# motorShield.net
KiCad netlist of a schematic drawn in EAGLE
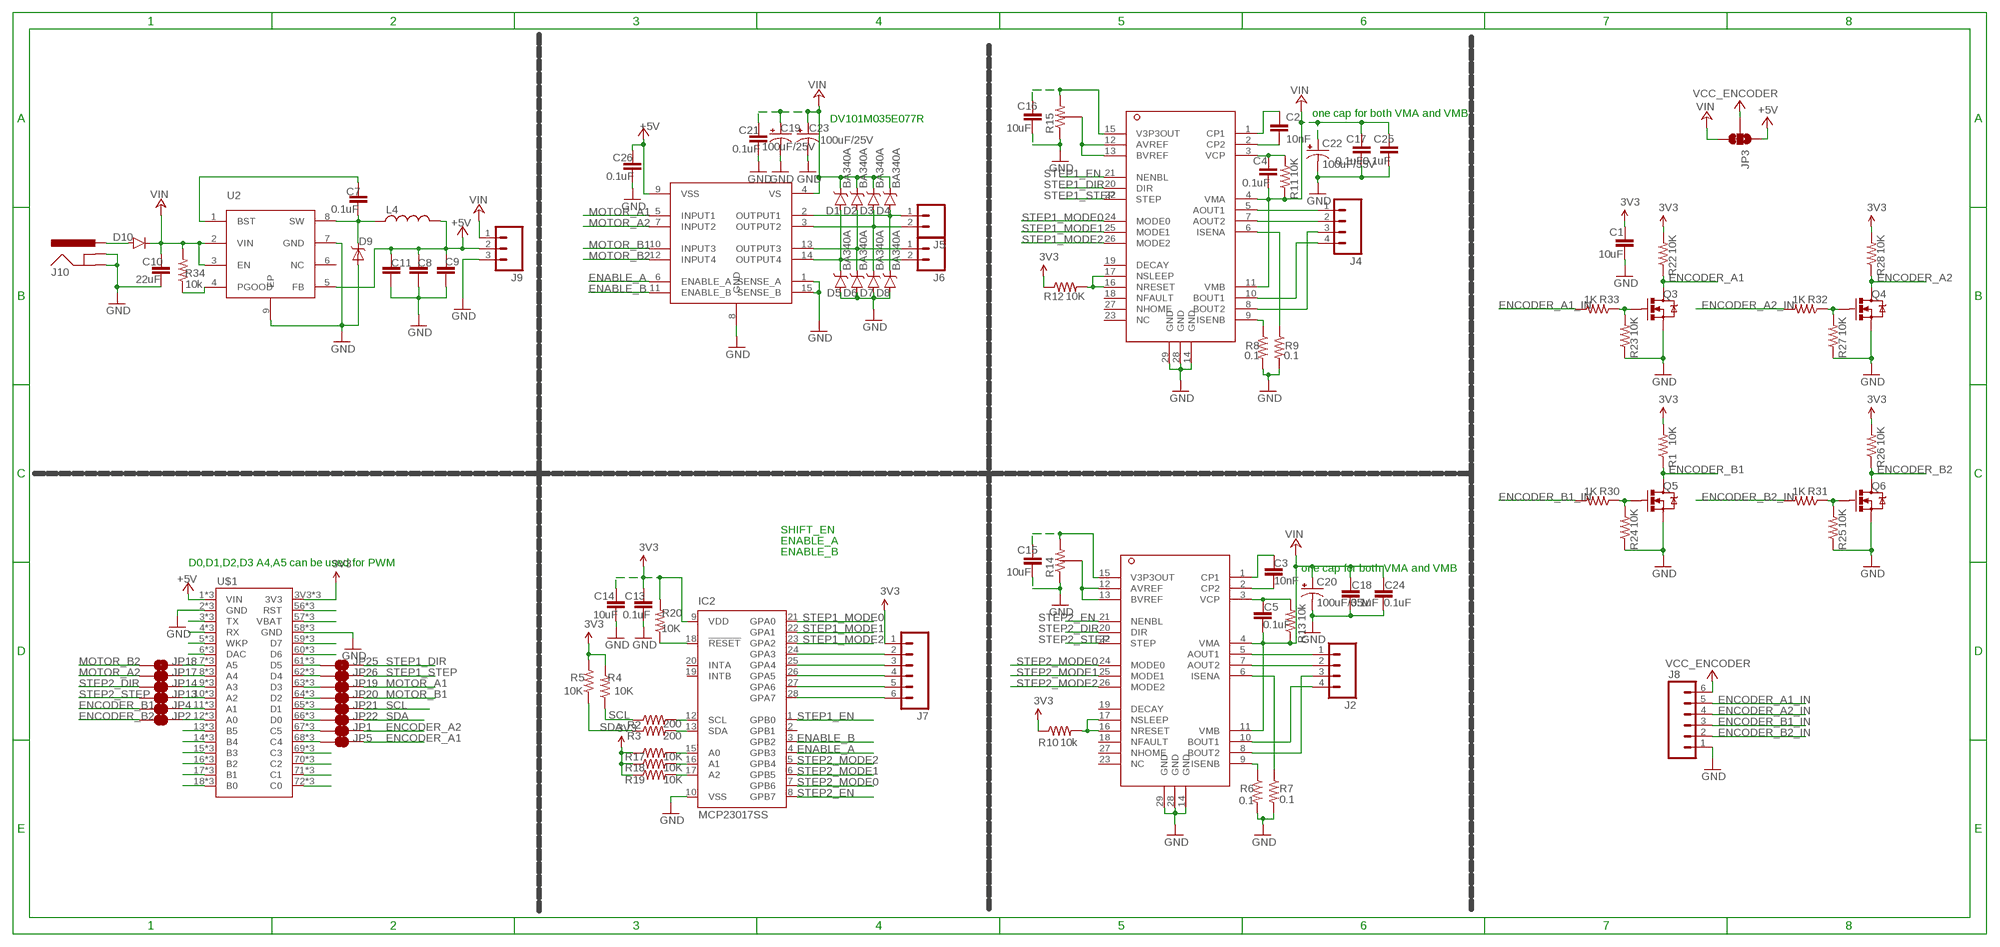
[diagram p0: schematic, sheet 1]

(export (version "E")
  (design (tool "Eeschema 10.0.6"))
  (components
    (comp (ref "C1")
      (value "10uF")
      (footprint "eagle-import:0603")
      (libsource (lib "eagle-import") (part "CAP_NONE_POL"))
    )
    (comp (ref "C2")
      (value "10nF")
      (footprint "eagle-import:0603")
      (libsource (lib "eagle-import") (part "CAP_NONE_POL"))
    )
    (comp (ref "C3")
      (value "10nF")
      (footprint "eagle-import:0603")
      (libsource (lib "eagle-import") (part "CAP_NONE_POL"))
    )
    (comp (ref "C4")
      (value "0.1uF")
      (footprint "eagle-import:0603")
      (libsource (lib "eagle-import") (part "CAP_NONE_POL"))
    )
    (comp (ref "C5")
      (value "0.1uF")
      (footprint "eagle-import:0603")
      (libsource (lib "eagle-import") (part "CAP_NONE_POL"))
    )
    (comp (ref "C7")
      (value "0.1uF")
      (footprint "eagle-import:0603-CAP")
      (libsource (lib "eagle-import") (part "0.1UF-100V-10%(0603)"))
    )
    (comp (ref "C8")
      (value "10UF10V10%(0805)")
      (footprint "eagle-import:0805-CAP")
      (libsource (lib "eagle-import") (part "10UF10V10%(0805)"))
    )
    (comp (ref "C9")
      (value "10UF10V10%(0805)")
      (footprint "eagle-import:0805-CAP")
      (libsource (lib "eagle-import") (part "10UF10V10%(0805)"))
    )
    (comp (ref "C10")
      (value "22uF")
      (footprint "eagle-import:1210")
      (libsource (lib "eagle-import") (part "22UF-16V-20%-(1210)"))
    )
    (comp (ref "C11")
      (value "10UF10V10%(0805)")
      (footprint "eagle-import:0805-CAP")
      (libsource (lib "eagle-import") (part "10UF10V10%(0805)"))
    )
    (comp (ref "C13")
      (value "0.1uF")
      (footprint "eagle-import:0603")
      (libsource (lib "eagle-import") (part "CAP_NONE_POL"))
    )
    (comp (ref "C14")
      (value "10uF")
      (footprint "eagle-import:0603")
      (libsource (lib "eagle-import") (part "CAP_NONE_POL"))
    )
    (comp (ref "C15")
      (value "10uF")
      (footprint "eagle-import:0603")
      (libsource (lib "eagle-import") (part "CAP_NONE_POL"))
    )
    (comp (ref "C16")
      (value "10uF")
      (footprint "eagle-import:0603")
      (libsource (lib "eagle-import") (part "CAP_NONE_POL"))
    )
    (comp (ref "C17")
      (value "0.1uF")
      (footprint "eagle-import:0603")
      (libsource (lib "eagle-import") (part "CAP_NONE_POL"))
    )
    (comp (ref "C18")
      (value "0.1uF")
      (footprint "eagle-import:0603")
      (libsource (lib "eagle-import") (part "CAP_NONE_POL"))
    )
    (comp (ref "C19")
      (value "100uF/25V")
      (footprint "eagle-import:PANASONIC_D")
      (libsource (lib "eagle-import") (part "CAP_POLD"))
    )
    (comp (ref "C20")
      (value "100uF/35V")
      (footprint "eagle-import:PANASONIC_D")
      (libsource (lib "eagle-import") (part "CAP_POLD"))
    )
    (comp (ref "C21")
      (value "0.1uF")
      (footprint "eagle-import:0603")
      (libsource (lib "eagle-import") (part "CAP_NONE_POL"))
    )
    (comp (ref "C22")
      (value "100uF/35V")
      (footprint "eagle-import:PANASONIC_D")
      (libsource (lib "eagle-import") (part "CAP_POLD"))
    )
    (comp (ref "C23")
      (value "100uF/25V")
      (footprint "eagle-import:PANASONIC_D")
      (libsource (lib "eagle-import") (part "CAP_POLD"))
    )
    (comp (ref "C24")
      (value "0.1uF")
      (footprint "eagle-import:0603")
      (libsource (lib "eagle-import") (part "CAP_NONE_POL"))
    )
    (comp (ref "C25")
      (value "0.1uF")
      (footprint "eagle-import:0603")
      (libsource (lib "eagle-import") (part "CAP_NONE_POL"))
    )
    (comp (ref "C26")
      (value "0.1uF")
      (footprint "eagle-import:0603")
      (libsource (lib "eagle-import") (part "CAP_NONE_POL"))
    )
    (comp (ref "D1")
      (value "BA340A")
      (footprint "eagle-import:SMA-DIODE")
      (libsource (lib "eagle-import") (part "B340A"))
    )
    (comp (ref "D2")
      (value "BA340A")
      (footprint "eagle-import:SMA-DIODE")
      (libsource (lib "eagle-import") (part "B340A"))
    )
    (comp (ref "D3")
      (value "BA340A")
      (footprint "eagle-import:SMA-DIODE")
      (libsource (lib "eagle-import") (part "B340A"))
    )
    (comp (ref "D4")
      (value "BA340A")
      (footprint "eagle-import:SMA-DIODE")
      (libsource (lib "eagle-import") (part "B340A"))
    )
    (comp (ref "D5")
      (value "BA340A")
      (footprint "eagle-import:SMA-DIODE")
      (libsource (lib "eagle-import") (part "B340A"))
    )
    (comp (ref "D6")
      (value "BA340A")
      (footprint "eagle-import:SMA-DIODE")
      (libsource (lib "eagle-import") (part "B340A"))
    )
    (comp (ref "D7")
      (value "BA340A")
      (footprint "eagle-import:SMA-DIODE")
      (libsource (lib "eagle-import") (part "B340A"))
    )
    (comp (ref "D8")
      (value "BA340A")
      (footprint "eagle-import:SMA-DIODE")
      (libsource (lib "eagle-import") (part "B340A"))
    )
    (comp (ref "D9")
      (value "DIODE_SCHOTTKYA")
      (footprint "eagle-import:DIODE_SMA")
      (libsource (lib "eagle-import") (part "DIODE_SCHOTTKYA"))
    )
    (comp (ref "D10")
      (value "DIODEB")
      (footprint "eagle-import:DIODE-DO-220AA_NT(SMP)")
      (libsource (lib "eagle-import") (part "DIODEB"))
    )
    (comp (ref "IC2")
      (value "MCP23017SS")
      (footprint "eagle-import:SSOP28")
      (libsource (lib "eagle-import") (part "MCP23017SS"))
    )
    (comp (ref "J2")
      (value "M04SCREW")
      (footprint "eagle-import:SCREWTERMINAL-3.5MM-4")
      (libsource (lib "eagle-import") (part "M04SCREW"))
    )
    (comp (ref "J4")
      (value "M04SCREW")
      (footprint "eagle-import:SCREWTERMINAL-3.5MM-4")
      (libsource (lib "eagle-import") (part "M04SCREW"))
    )
    (comp (ref "J5")
      (value "M023.5MM_LOCK")
      (footprint "eagle-import:SCREWTERMINAL-3.5MM-2_LOCK")
      (libsource (lib "eagle-import") (part "M023.5MM_LOCK"))
    )
    (comp (ref "J6")
      (value "M023.5MM_LOCK")
      (footprint "eagle-import:SCREWTERMINAL-3.5MM-2_LOCK")
      (libsource (lib "eagle-import") (part "M023.5MM_LOCK"))
    )
    (comp (ref "J7")
      (value "M06POLAR")
      (footprint "eagle-import:MOLEX-1X6")
      (libsource (lib "eagle-import") (part "M06POLAR"))
    )
    (comp (ref "J8")
      (value "M06POLAR")
      (footprint "eagle-import:MOLEX-1X6")
      (libsource (lib "eagle-import") (part "M06POLAR"))
    )
    (comp (ref "J9")
      (value "M03SCREW")
      (footprint "eagle-import:SCREWTERMINAL-3.5MM-3")
      (libsource (lib "eagle-import") (part "M03SCREW"))
    )
    (comp (ref "J10")
      (value "POWER_JACKPTH")
      (footprint "eagle-import:POWER_JACK_PTH")
      (libsource (lib "eagle-import") (part "POWER_JACKPTH"))
    )
    (comp (ref "JP1")
      (value "JUMPER-PAD-2-NC_BY_TRACENO_SILK")
      (footprint "eagle-import:PAD-JUMPER-2-NC_BY_TRACE_NO_SILK")
      (libsource (lib "eagle-import") (part "JUMPER-PAD-2-NC_BY_TRACENO_SILK"))
    )
    (comp (ref "JP2")
      (value "JUMPER-PAD-2-NC_BY_TRACENO_SILK")
      (footprint "eagle-import:PAD-JUMPER-2-NC_BY_TRACE_NO_SILK")
      (libsource (lib "eagle-import") (part "JUMPER-PAD-2-NC_BY_TRACENO_SILK"))
    )
    (comp (ref "JP3")
      (value "JUMPER-PAD-3-2OF3_NC_BY_TRACE_LARGE")
      (footprint "eagle-import:PAD-JUMPER-3-2OF3_NC_BY_TRACE_YES_SILK_LARGE")
      (libsource (lib "eagle-import") (part "JUMPER-PAD-3-2OF3_NC_BY_TRACE_LARGE"))
    )
    (comp (ref "JP4")
      (value "JUMPER-PAD-2-NC_BY_TRACENO_SILK")
      (footprint "eagle-import:PAD-JUMPER-2-NC_BY_TRACE_NO_SILK")
      (libsource (lib "eagle-import") (part "JUMPER-PAD-2-NC_BY_TRACENO_SILK"))
    )
    (comp (ref "JP5")
      (value "JUMPER-PAD-2-NC_BY_TRACENO_SILK")
      (footprint "eagle-import:PAD-JUMPER-2-NC_BY_TRACE_NO_SILK")
      (libsource (lib "eagle-import") (part "JUMPER-PAD-2-NC_BY_TRACENO_SILK"))
    )
    (comp (ref "JP13")
      (value "JUMPER-PAD-2-NC_BY_TRACENO_SILK")
      (footprint "eagle-import:PAD-JUMPER-2-NC_BY_TRACE_NO_SILK")
      (libsource (lib "eagle-import") (part "JUMPER-PAD-2-NC_BY_TRACENO_SILK"))
    )
    (comp (ref "JP14")
      (value "JUMPER-PAD-2-NC_BY_TRACENO_SILK")
      (footprint "eagle-import:PAD-JUMPER-2-NC_BY_TRACE_NO_SILK")
      (libsource (lib "eagle-import") (part "JUMPER-PAD-2-NC_BY_TRACENO_SILK"))
    )
    (comp (ref "JP17")
      (value "JUMPER-PAD-2-NC_BY_TRACENO_SILK")
      (footprint "eagle-import:PAD-JUMPER-2-NC_BY_TRACE_NO_SILK")
      (libsource (lib "eagle-import") (part "JUMPER-PAD-2-NC_BY_TRACENO_SILK"))
    )
    (comp (ref "JP18")
      (value "JUMPER-PAD-2-NC_BY_TRACENO_SILK")
      (footprint "eagle-import:PAD-JUMPER-2-NC_BY_TRACE_NO_SILK")
      (libsource (lib "eagle-import") (part "JUMPER-PAD-2-NC_BY_TRACENO_SILK"))
    )
    (comp (ref "JP19")
      (value "JUMPER-PAD-2-NC_BY_TRACENO_SILK")
      (footprint "eagle-import:PAD-JUMPER-2-NC_BY_TRACE_NO_SILK")
      (libsource (lib "eagle-import") (part "JUMPER-PAD-2-NC_BY_TRACENO_SILK"))
    )
    (comp (ref "JP20")
      (value "JUMPER-PAD-2-NC_BY_TRACENO_SILK")
      (footprint "eagle-import:PAD-JUMPER-2-NC_BY_TRACE_NO_SILK")
      (libsource (lib "eagle-import") (part "JUMPER-PAD-2-NC_BY_TRACENO_SILK"))
    )
    (comp (ref "JP21")
      (value "JUMPER-PAD-2-NC_BY_TRACENO_SILK")
      (footprint "eagle-import:PAD-JUMPER-2-NC_BY_TRACE_NO_SILK")
      (libsource (lib "eagle-import") (part "JUMPER-PAD-2-NC_BY_TRACENO_SILK"))
    )
    (comp (ref "JP22")
      (value "JUMPER-PAD-2-NC_BY_TRACENO_SILK")
      (footprint "eagle-import:PAD-JUMPER-2-NC_BY_TRACE_NO_SILK")
      (libsource (lib "eagle-import") (part "JUMPER-PAD-2-NC_BY_TRACENO_SILK"))
    )
    (comp (ref "JP25")
      (value "JUMPER-PAD-2-NC_BY_TRACENO_SILK")
      (footprint "eagle-import:PAD-JUMPER-2-NC_BY_TRACE_NO_SILK")
      (libsource (lib "eagle-import") (part "JUMPER-PAD-2-NC_BY_TRACENO_SILK"))
    )
    (comp (ref "JP26")
      (value "JUMPER-PAD-2-NC_BY_TRACENO_SILK")
      (footprint "eagle-import:PAD-JUMPER-2-NC_BY_TRACE_NO_SILK")
      (libsource (lib "eagle-import") (part "JUMPER-PAD-2-NC_BY_TRACENO_SILK"))
    )
    (comp (ref "L4")
      (value "INDUCTOR4818")
      (footprint "eagle-import:I4818")
      (libsource (lib "eagle-import") (part "INDUCTOR4818"))
    )
    (comp (ref "Q3")
      (value "MOSFET-NCHANNELBSS138")
      (footprint "eagle-import:SOT23")
      (libsource (lib "eagle-import") (part "MOSFET-NCHANNELBSS138"))
    )
    (comp (ref "Q4")
      (value "MOSFET-NCHANNELBSS138")
      (footprint "eagle-import:SOT23")
      (libsource (lib "eagle-import") (part "MOSFET-NCHANNELBSS138"))
    )
    (comp (ref "Q5")
      (value "MOSFET-NCHANNELBSS138")
      (footprint "eagle-import:SOT23")
      (libsource (lib "eagle-import") (part "MOSFET-NCHANNELBSS138"))
    )
    (comp (ref "Q6")
      (value "MOSFET-NCHANNELBSS138")
      (footprint "eagle-import:SOT23")
      (libsource (lib "eagle-import") (part "MOSFET-NCHANNELBSS138"))
    )
    (comp (ref "R1")
      (value "10K")
      (footprint "eagle-import:R0603")
      (libsource (lib "eagle-import") (part "R-US_A"))
    )
    (comp (ref "R2")
      (value "200")
      (footprint "eagle-import:R0603")
      (libsource (lib "eagle-import") (part "R-US_A"))
    )
    (comp (ref "R3")
      (value "200")
      (footprint "eagle-import:R0603")
      (libsource (lib "eagle-import") (part "R-US_A"))
    )
    (comp (ref "R4")
      (value "10K")
      (footprint "eagle-import:R0603")
      (libsource (lib "eagle-import") (part "R-US_A"))
    )
    (comp (ref "R5")
      (value "10K")
      (footprint "eagle-import:R0603")
      (libsource (lib "eagle-import") (part "R-US_A"))
    )
    (comp (ref "R6")
      (value "0.1")
      (footprint "eagle-import:M1206")
      (libsource (lib "eagle-import") (part "R-US_M1206"))
    )
    (comp (ref "R7")
      (value "0.1")
      (footprint "eagle-import:M1206")
      (libsource (lib "eagle-import") (part "R-US_M1206"))
    )
    (comp (ref "R8")
      (value "0.1")
      (footprint "eagle-import:M1206")
      (libsource (lib "eagle-import") (part "R-US_M1206"))
    )
    (comp (ref "R9")
      (value "0.1")
      (footprint "eagle-import:M1206")
      (libsource (lib "eagle-import") (part "R-US_M1206"))
    )
    (comp (ref "R10")
      (value "10k")
      (footprint "eagle-import:R0603")
      (libsource (lib "eagle-import") (part "R-US_A"))
    )
    (comp (ref "R11")
      (value "10K")
      (footprint "eagle-import:R0603")
      (libsource (lib "eagle-import") (part "R-US_A"))
    )
    (comp (ref "R12")
      (value "10K")
      (footprint "eagle-import:R0603")
      (libsource (lib "eagle-import") (part "R-US_A"))
    )
    (comp (ref "R13")
      (value "10k")
      (footprint "eagle-import:R0603")
      (libsource (lib "eagle-import") (part "R-US_A"))
    )
    (comp (ref "R14")
      (value "POTENTIAL_RESISTOR")
      (footprint "eagle-import:POTENTIAL_RESISTOR_2")
      (libsource (lib "eagle-import") (part "POTENTIAL_RESISTOR"))
    )
    (comp (ref "R15")
      (value "POTENTIAL_RESISTOR")
      (footprint "eagle-import:POTENTIAL_RESISTOR_2")
      (libsource (lib "eagle-import") (part "POTENTIAL_RESISTOR"))
    )
    (comp (ref "R17")
      (value "10K")
      (footprint "eagle-import:R0603")
      (libsource (lib "eagle-import") (part "R-US_A"))
    )
    (comp (ref "R18")
      (value "10K")
      (footprint "eagle-import:R0603")
      (libsource (lib "eagle-import") (part "R-US_A"))
    )
    (comp (ref "R19")
      (value "10K")
      (footprint "eagle-import:R0603")
      (libsource (lib "eagle-import") (part "R-US_A"))
    )
    (comp (ref "R20")
      (value "10K")
      (footprint "eagle-import:R0603")
      (libsource (lib "eagle-import") (part "R-US_A"))
    )
    (comp (ref "R22")
      (value "10K")
      (footprint "eagle-import:R0603")
      (libsource (lib "eagle-import") (part "R-US_A"))
    )
    (comp (ref "R23")
      (value "10K")
      (footprint "eagle-import:R0603")
      (libsource (lib "eagle-import") (part "R-US_A"))
    )
    (comp (ref "R24")
      (value "10K")
      (footprint "eagle-import:R0603")
      (libsource (lib "eagle-import") (part "R-US_A"))
    )
    (comp (ref "R25")
      (value "10K")
      (footprint "eagle-import:R0603")
      (libsource (lib "eagle-import") (part "R-US_A"))
    )
    (comp (ref "R26")
      (value "10K")
      (footprint "eagle-import:R0603")
      (libsource (lib "eagle-import") (part "R-US_A"))
    )
    (comp (ref "R27")
      (value "10K")
      (footprint "eagle-import:R0603")
      (libsource (lib "eagle-import") (part "R-US_A"))
    )
    (comp (ref "R28")
      (value "10K")
      (footprint "eagle-import:R0603")
      (libsource (lib "eagle-import") (part "R-US_A"))
    )
    (comp (ref "R30")
      (value "1K")
      (footprint "eagle-import:R0603")
      (libsource (lib "eagle-import") (part "R-US_A"))
    )
    (comp (ref "R31")
      (value "1K")
      (footprint "eagle-import:R0603")
      (libsource (lib "eagle-import") (part "R-US_A"))
    )
    (comp (ref "R32")
      (value "1K")
      (footprint "eagle-import:R0603")
      (libsource (lib "eagle-import") (part "R-US_A"))
    )
    (comp (ref "R33")
      (value "1K")
      (footprint "eagle-import:R0603")
      (libsource (lib "eagle-import") (part "R-US_A"))
    )
    (comp (ref "R34")
      (value "10k")
      (footprint "eagle-import:0603-RES")
      (libsource (lib "eagle-import") (part "20OHM1/10W1%(0603)SMD"))
    )
    (comp (ref "U$1")
      (value "ELECTRONDUALROW")
      (footprint "eagle-import:ELECTRON_DUAL-ROW")
      (libsource (lib "eagle-import") (part "ELECTRONDUALROW"))
    )
    (comp (ref "U2")
      (value "ADP2303")
      (footprint "eagle-import:ADP2302")
      (libsource (lib "eagle-import") (part "ADP2303"))
    )
    (comp (ref "U?1")
      (value "DRV8825")
      (footprint "eagle-import:DRV8825")
      (libsource (lib "eagle-import") (part "DRV8825"))
    )
    (comp (ref "U?2")
      (value "L298")
      (footprint "eagle-import:L298")
      (libsource (lib "eagle-import") (part "L298"))
    )
    (comp (ref "U?3")
      (value "DRV8825")
      (footprint "eagle-import:DRV8825")
      (libsource (lib "eagle-import") (part "DRV8825"))
    )
  )
  (nets
    (net (code "1") (name "+5V") (class "Default")
      (node (ref "C11") (pin "1") (pinfunction "1_1") (pintype "passive"))
      (node (ref "C26") (pin "1") (pinfunction "ANODE_1") (pintype "passive"))
      (node (ref "C8") (pin "2") (pinfunction "2_2") (pintype "passive"))
      (node (ref "C9") (pin "2") (pinfunction "2_2") (pintype "passive"))
      (node (ref "J8") (pin "6") (pinfunction "6_6") (pintype "passive"))
      (node (ref "J9") (pin "2") (pinfunction "2_2") (pintype "passive"))
      (node (ref "JP3") (pin "1") (pinfunction "1_1") (pintype "passive"))
      (node (ref "JP3") (pin "2") (pinfunction "2_2") (pintype "passive"))
      (node (ref "L4") (pin "2") (pinfunction "2_2") (pintype "passive"))
      (node (ref "U$1") (pin "1") (pinfunction "VIN_1") (pintype "power_in"))
      (node (ref "U$1") (pin "37") (pinfunction "VIN_37") (pintype "power_in"))
      (node (ref "U$1") (pin "VIN") (pinfunction "VIN_VIN") (pintype "power_in"))
      (node (ref "U2") (pin "5") (pinfunction "FB_5") (pintype "bidirectional"))
      (node (ref "U?2") (pin "9") (pinfunction "VSS_9") (pintype "bidirectional"))
    )
    (net (code "2") (name "/ENABLE_A") (class "Default")
      (node (ref "IC2") (pin "4") (pinfunction "GPB3_4") (pintype "bidirectional"))
      (node (ref "U?2") (pin "6") (pinfunction "ENABLE_A_6") (pintype "bidirectional"))
    )
    (net (code "3") (name "/ENABLE_B") (class "Default")
      (node (ref "IC2") (pin "3") (pinfunction "GPB2_3") (pintype "bidirectional"))
      (node (ref "U?2") (pin "11") (pinfunction "ENABLE_B_11") (pintype "bidirectional"))
    )
    (net (code "4") (name "/ENCODER_A1") (class "Default")
      (node (ref "JP5") (pin "2") (pinfunction "2_2") (pintype "passive"))
      (node (ref "Q3") (pin "3") (pinfunction "D_3") (pintype "passive"))
      (node (ref "R22") (pin "1") (pinfunction "1_1") (pintype "passive"))
    )
    (net (code "5") (name "/ENCODER_A1_IN") (class "Default")
      (node (ref "J8") (pin "5") (pinfunction "5_5") (pintype "passive"))
      (node (ref "R33") (pin "2") (pinfunction "2_2") (pintype "passive"))
    )
    (net (code "6") (name "/ENCODER_A2") (class "Default")
      (node (ref "JP1") (pin "2") (pinfunction "2_2") (pintype "passive"))
      (node (ref "Q4") (pin "3") (pinfunction "D_3") (pintype "passive"))
      (node (ref "R28") (pin "1") (pinfunction "1_1") (pintype "passive"))
    )
    (net (code "7") (name "/ENCODER_A2_IN") (class "Default")
      (node (ref "J8") (pin "4") (pinfunction "4_4") (pintype "passive"))
      (node (ref "R32") (pin "2") (pinfunction "2_2") (pintype "passive"))
    )
    (net (code "8") (name "/ENCODER_B1") (class "Default")
      (node (ref "JP4") (pin "1") (pinfunction "1_1") (pintype "passive"))
      (node (ref "Q5") (pin "3") (pinfunction "D_3") (pintype "passive"))
      (node (ref "R1") (pin "1") (pinfunction "1_1") (pintype "passive"))
    )
    (net (code "9") (name "/ENCODER_B1_IN") (class "Default")
      (node (ref "J8") (pin "3") (pinfunction "3_3") (pintype "passive"))
      (node (ref "R30") (pin "2") (pinfunction "2_2") (pintype "passive"))
    )
    (net (code "10") (name "/ENCODER_B2") (class "Default")
      (node (ref "JP2") (pin "1") (pinfunction "1_1") (pintype "passive"))
      (node (ref "Q6") (pin "3") (pinfunction "D_3") (pintype "passive"))
      (node (ref "R26") (pin "1") (pinfunction "1_1") (pintype "passive"))
    )
    (net (code "11") (name "/ENCODER_B2_IN") (class "Default")
      (node (ref "J8") (pin "2") (pinfunction "2_2") (pintype "passive"))
      (node (ref "R31") (pin "2") (pinfunction "2_2") (pintype "passive"))
    )
    (net (code "12") (name "/MOTOR_A1") (class "Default")
      (node (ref "JP19") (pin "2") (pinfunction "2_2") (pintype "passive"))
      (node (ref "U?2") (pin "5") (pinfunction "INPUT1_5") (pintype "bidirectional"))
    )
    (net (code "13") (name "/MOTOR_A2") (class "Default")
      (node (ref "JP17") (pin "1") (pinfunction "1_1") (pintype "passive"))
      (node (ref "U?2") (pin "7") (pinfunction "INPUT2_7") (pintype "bidirectional"))
    )
    (net (code "14") (name "/MOTOR_B1") (class "Default")
      (node (ref "JP20") (pin "2") (pinfunction "2_2") (pintype "passive"))
      (node (ref "U?2") (pin "10") (pinfunction "INPUT3_10") (pintype "bidirectional"))
    )
    (net (code "15") (name "/MOTOR_B2") (class "Default")
      (node (ref "JP18") (pin "1") (pinfunction "1_1") (pintype "passive"))
      (node (ref "U?2") (pin "12") (pinfunction "INPUT4_12") (pintype "bidirectional"))
    )
    (net (code "16") (name "/SCL") (class "Default")
      (node (ref "JP21") (pin "2") (pinfunction "2_2") (pintype "passive"))
      (node (ref "R2") (pin "1") (pinfunction "1_1") (pintype "passive"))
      (node (ref "R4") (pin "1") (pinfunction "1_1") (pintype "passive"))
    )
    (net (code "17") (name "/SDA") (class "Default")
      (node (ref "JP22") (pin "2") (pinfunction "2_2") (pintype "passive"))
      (node (ref "R3") (pin "1") (pinfunction "1_1") (pintype "passive"))
      (node (ref "R5") (pin "1") (pinfunction "1_1") (pintype "passive"))
    )
    (net (code "18") (name "/STEP1_DIR") (class "Default")
      (node (ref "JP25") (pin "2") (pinfunction "2_2") (pintype "passive"))
      (node (ref "U?1") (pin "20") (pinfunction "DIR_20") (pintype "bidirectional"))
    )
    (net (code "19") (name "/STEP1_EN") (class "Default")
      (node (ref "IC2") (pin "1") (pinfunction "GPB0_1") (pintype "bidirectional"))
      (node (ref "U?1") (pin "21") (pinfunction "NENBL_21") (pintype "bidirectional"))
    )
    (net (code "20") (name "/STEP1_MODE0") (class "Default")
      (node (ref "IC2") (pin "21") (pinfunction "GPA0_21") (pintype "bidirectional"))
      (node (ref "U?1") (pin "24") (pinfunction "MODE0_24") (pintype "bidirectional"))
    )
    (net (code "21") (name "/STEP1_MODE1") (class "Default")
      (node (ref "IC2") (pin "22") (pinfunction "GPA1_22") (pintype "bidirectional"))
      (node (ref "U?1") (pin "25") (pinfunction "MODE1_25") (pintype "bidirectional"))
    )
    (net (code "22") (name "/STEP1_MODE2") (class "Default")
      (node (ref "IC2") (pin "23") (pinfunction "GPA2_23") (pintype "bidirectional"))
      (node (ref "U?1") (pin "26") (pinfunction "MODE2_26") (pintype "bidirectional"))
    )
    (net (code "23") (name "/STEP1_STEP") (class "Default")
      (node (ref "JP26") (pin "2") (pinfunction "2_2") (pintype "passive"))
      (node (ref "U?1") (pin "22") (pinfunction "STEP_22") (pintype "bidirectional"))
    )
    (net (code "24") (name "/STEP2_DIR") (class "Default")
      (node (ref "JP14") (pin "1") (pinfunction "1_1") (pintype "passive"))
      (node (ref "U?3") (pin "20") (pinfunction "DIR_20") (pintype "bidirectional"))
    )
    (net (code "25") (name "/STEP2_EN") (class "Default")
      (node (ref "IC2") (pin "8") (pinfunction "GPB7_8") (pintype "bidirectional"))
      (node (ref "U?3") (pin "21") (pinfunction "NENBL_21") (pintype "bidirectional"))
    )
    (net (code "26") (name "/STEP2_MODE0") (class "Default")
      (node (ref "IC2") (pin "7") (pinfunction "GPB6_7") (pintype "bidirectional"))
      (node (ref "U?3") (pin "24") (pinfunction "MODE0_24") (pintype "bidirectional"))
    )
    (net (code "27") (name "/STEP2_MODE1") (class "Default")
      (node (ref "IC2") (pin "6") (pinfunction "GPB5_6") (pintype "bidirectional"))
      (node (ref "U?3") (pin "25") (pinfunction "MODE1_25") (pintype "bidirectional"))
    )
    (net (code "28") (name "/STEP2_MODE2") (class "Default")
      (node (ref "IC2") (pin "5") (pinfunction "GPB4_5") (pintype "bidirectional"))
      (node (ref "U?3") (pin "26") (pinfunction "MODE2_26") (pintype "bidirectional"))
    )
    (net (code "29") (name "/STEP2_STEP") (class "Default")
      (node (ref "JP13") (pin "1") (pinfunction "1_1") (pintype "passive"))
      (node (ref "U?3") (pin "22") (pinfunction "STEP_22") (pintype "bidirectional"))
    )
    (net (code "30") (name "3V3") (class "Default")
      (node (ref "C1") (pin "1") (pinfunction "ANODE_1") (pintype "passive"))
      (node (ref "C13") (pin "1") (pinfunction "ANODE_1") (pintype "passive"))
      (node (ref "C14") (pin "1") (pinfunction "ANODE_1") (pintype "passive"))
      (node (ref "IC2") (pin "9") (pinfunction "VDD_9") (pintype "power_in"))
      (node (ref "J7") (pin "1") (pinfunction "1_1") (pintype "passive"))
      (node (ref "R1") (pin "2") (pinfunction "2_2") (pintype "passive"))
      (node (ref "R10") (pin "1") (pinfunction "1_1") (pintype "passive"))
      (node (ref "R12") (pin "1") (pinfunction "1_1") (pintype "passive"))
      (node (ref "R17") (pin "1") (pinfunction "1_1") (pintype "passive"))
      (node (ref "R18") (pin "1") (pinfunction "1_1") (pintype "passive"))
      (node (ref "R19") (pin "1") (pinfunction "1_1") (pintype "passive"))
      (node (ref "R20") (pin "2") (pinfunction "2_2") (pintype "passive"))
      (node (ref "R22") (pin "2") (pinfunction "2_2") (pintype "passive"))
      (node (ref "R26") (pin "2") (pinfunction "2_2") (pintype "passive"))
      (node (ref "R28") (pin "2") (pinfunction "2_2") (pintype "passive"))
      (node (ref "R4") (pin "2") (pinfunction "2_2") (pintype "passive"))
      (node (ref "R5") (pin "2") (pinfunction "2_2") (pintype "passive"))
      (node (ref "U$1") (pin "3V3") (pinfunction "3V3_3V3") (pintype "power_in"))
      (node (ref "U$1") (pin "55") (pinfunction "3V3_55") (pintype "power_in"))
      (node (ref "U$1") (pin "91") (pinfunction "3V3_91") (pintype "power_in"))
    )
    (net (code "31") (name "GND") (class "Default")
      (node (ref "C1") (pin "2") (pinfunction "CATHODE_2") (pintype "passive"))
      (node (ref "C10") (pin "2") (pinfunction "2_2") (pintype "passive"))
      (node (ref "C11") (pin "2") (pinfunction "2_2") (pintype "passive"))
      (node (ref "C13") (pin "2") (pinfunction "CATHODE_2") (pintype "passive"))
      (node (ref "C14") (pin "2") (pinfunction "CATHODE_2") (pintype "passive"))
      (node (ref "C15") (pin "2") (pinfunction "CATHODE_2") (pintype "passive"))
      (node (ref "C16") (pin "2") (pinfunction "CATHODE_2") (pintype "passive"))
      (node (ref "C17") (pin "2") (pinfunction "CATHODE_2") (pintype "passive"))
      (node (ref "C18") (pin "2") (pinfunction "CATHODE_2") (pintype "passive"))
      (node (ref "C19") (pin "-") (pinfunction "-_-") (pintype "passive"))
      (node (ref "C20") (pin "-") (pinfunction "-_-") (pintype "passive"))
      (node (ref "C21") (pin "2") (pinfunction "CATHODE_2") (pintype "passive"))
      (node (ref "C22") (pin "-") (pinfunction "-_-") (pintype "passive"))
      (node (ref "C23") (pin "-") (pinfunction "-_-") (pintype "passive"))
      (node (ref "C24") (pin "2") (pinfunction "CATHODE_2") (pintype "passive"))
      (node (ref "C25") (pin "2") (pinfunction "CATHODE_2") (pintype "passive"))
      (node (ref "C26") (pin "2") (pinfunction "CATHODE_2") (pintype "passive"))
      (node (ref "C8") (pin "1") (pinfunction "1_1") (pintype "passive"))
      (node (ref "C9") (pin "1") (pinfunction "1_1") (pintype "passive"))
      (node (ref "D5") (pin "A") (pinfunction "A_A") (pintype "passive"))
      (node (ref "D6") (pin "A") (pinfunction "A_A") (pintype "passive"))
      (node (ref "D7") (pin "A") (pinfunction "A_A") (pintype "passive"))
      (node (ref "D8") (pin "A") (pinfunction "A_A") (pintype "passive"))
      (node (ref "D9") (pin "ANODE") (pinfunction "ANODE_ANODE") (pintype "passive"))
      (node (ref "IC2") (pin "10") (pinfunction "VSS_10") (pintype "power_in"))
      (node (ref "J10") (pin "GND") (pinfunction "GND_GND") (pintype "bidirectional"))
      (node (ref "J10") (pin "GNDBREAK") (pinfunction "GNDBREAK_GNDBREAK") (pintype "bidirectional"))
      (node (ref "J8") (pin "1") (pinfunction "1_1") (pintype "passive"))
      (node (ref "J9") (pin "3") (pinfunction "3_3") (pintype "passive"))
      (node (ref "Q3") (pin "2") (pinfunction "S_2") (pintype "passive"))
      (node (ref "Q4") (pin "2") (pinfunction "S_2") (pintype "passive"))
      (node (ref "Q5") (pin "2") (pinfunction "S_2") (pintype "passive"))
      (node (ref "Q6") (pin "2") (pinfunction "S_2") (pintype "passive"))
      (node (ref "R14") (pin "1") (pinfunction "1_1") (pintype "passive"))
      (node (ref "R15") (pin "1") (pinfunction "1_1") (pintype "passive"))
      (node (ref "R23") (pin "1") (pinfunction "1_1") (pintype "passive"))
      (node (ref "R24") (pin "1") (pinfunction "1_1") (pintype "passive"))
      (node (ref "R25") (pin "1") (pinfunction "1_1") (pintype "passive"))
      (node (ref "R27") (pin "1") (pinfunction "1_1") (pintype "passive"))
      (node (ref "R6") (pin "2") (pinfunction "2_2") (pintype "passive"))
      (node (ref "R7") (pin "2") (pinfunction "2_2") (pintype "passive"))
      (node (ref "R8") (pin "2") (pinfunction "2_2") (pintype "passive"))
      (node (ref "R9") (pin "2") (pinfunction "2_2") (pintype "passive"))
      (node (ref "U$1") (pin "2") (pinfunction "GND_2") (pintype "power_in"))
      (node (ref "U$1") (pin "38") (pinfunction "GND_38") (pintype "power_in"))
      (node (ref "U$1") (pin "58") (pinfunction "GND_58") (pintype "power_in"))
      (node (ref "U$1") (pin "94") (pinfunction "GND_94") (pintype "power_in"))
      (node (ref "U$1") (pin "GND") (pinfunction "GND_GND") (pintype "power_in"))
      (node (ref "U$1") (pin "GND@2") (pinfunction "GND_GND@2") (pintype "power_in"))
      (node (ref "U2") (pin "7") (pinfunction "GND_7") (pintype "bidirectional"))
      (node (ref "U2") (pin "9") (pinfunction "EP_9") (pintype "bidirectional"))
      (node (ref "U?1") (pin "14") (pinfunction "GND_14") (pintype "bidirectional"))
      (node (ref "U?1") (pin "28") (pinfunction "GND_28") (pintype "bidirectional"))
      (node (ref "U?1") (pin "29") (pinfunction "GND_29") (pintype "bidirectional"))
      (node (ref "U?2") (pin "1") (pinfunction "SENSE_A_1") (pintype "bidirectional"))
      (node (ref "U?2") (pin "15") (pinfunction "SENSE_B_15") (pintype "bidirectional"))
      (node (ref "U?2") (pin "8") (pinfunction "GND_8") (pintype "bidirectional"))
      (node (ref "U?3") (pin "14") (pinfunction "GND_14") (pintype "bidirectional"))
      (node (ref "U?3") (pin "28") (pinfunction "GND_28") (pintype "bidirectional"))
      (node (ref "U?3") (pin "29") (pinfunction "GND_29") (pintype "bidirectional"))
    )
    (net (code "32") (name "Net-(C2-ANODE)") (class "Default")
      (node (ref "C2") (pin "1") (pinfunction "ANODE_1") (pintype "passive"))
      (node (ref "U?1") (pin "1") (pinfunction "CP1_1") (pintype "bidirectional"))
    )
    (net (code "33") (name "Net-(C2-CATHODE)") (class "Default")
      (node (ref "C2") (pin "2") (pinfunction "CATHODE_2") (pintype "passive"))
      (node (ref "U?1") (pin "2") (pinfunction "CP2_2") (pintype "bidirectional"))
    )
    (net (code "34") (name "Net-(C3-ANODE)") (class "Default")
      (node (ref "C3") (pin "1") (pinfunction "ANODE_1") (pintype "passive"))
      (node (ref "U?3") (pin "1") (pinfunction "CP1_1") (pintype "bidirectional"))
    )
    (net (code "35") (name "Net-(C3-CATHODE)") (class "Default")
      (node (ref "C3") (pin "2") (pinfunction "CATHODE_2") (pintype "passive"))
      (node (ref "U?3") (pin "2") (pinfunction "CP2_2") (pintype "bidirectional"))
    )
    (net (code "36") (name "Net-(C4-ANODE)") (class "Default")
      (node (ref "C4") (pin "1") (pinfunction "ANODE_1") (pintype "passive"))
      (node (ref "R11") (pin "2") (pinfunction "2_2") (pintype "passive"))
      (node (ref "U?1") (pin "3") (pinfunction "VCP_3") (pintype "bidirectional"))
    )
    (net (code "37") (name "Net-(C5-ANODE)") (class "Default")
      (node (ref "C5") (pin "1") (pinfunction "ANODE_1") (pintype "passive"))
      (node (ref "R13") (pin "2") (pinfunction "2_2") (pintype "passive"))
      (node (ref "U?3") (pin "3") (pinfunction "VCP_3") (pintype "bidirectional"))
    )
    (net (code "38") (name "Net-(C15-ANODE)") (class "Default")
      (node (ref "C15") (pin "1") (pinfunction "ANODE_1") (pintype "passive"))
      (node (ref "R14") (pin "2") (pinfunction "2_2") (pintype "passive"))
      (node (ref "U?3") (pin "15") (pinfunction "V3P3OUT_15") (pintype "bidirectional"))
    )
    (net (code "39") (name "Net-(C16-ANODE)") (class "Default")
      (node (ref "C16") (pin "1") (pinfunction "ANODE_1") (pintype "passive"))
      (node (ref "R15") (pin "2") (pinfunction "2_2") (pintype "passive"))
      (node (ref "U?1") (pin "15") (pinfunction "V3P3OUT_15") (pintype "bidirectional"))
    )
    (net (code "40") (name "Net-(D10-PadANODE)") (class "Default")
      (node (ref "D10") (pin "ANODE") (pinfunction "ANODE_ANODE") (pintype "bidirectional"))
      (node (ref "J10") (pin "PWR") (pinfunction "PWR_PWR") (pintype "bidirectional"))
    )
    (net (code "41") (name "Net-(IC2-A0)") (class "Default")
      (node (ref "IC2") (pin "15") (pinfunction "A0_15") (pintype "input"))
      (node (ref "R17") (pin "2") (pinfunction "2_2") (pintype "passive"))
    )
    (net (code "42") (name "Net-(IC2-A1)") (class "Default")
      (node (ref "IC2") (pin "16") (pinfunction "A1_16") (pintype "input"))
      (node (ref "R18") (pin "2") (pinfunction "2_2") (pintype "passive"))
    )
    (net (code "43") (name "Net-(IC2-A2)") (class "Default")
      (node (ref "IC2") (pin "17") (pinfunction "A2_17") (pintype "input"))
      (node (ref "R19") (pin "2") (pinfunction "2_2") (pintype "passive"))
    )
    (net (code "44") (name "Net-(IC2-GPA3)") (class "Default")
      (node (ref "IC2") (pin "24") (pinfunction "GPA3_24") (pintype "bidirectional"))
      (node (ref "J7") (pin "2") (pinfunction "2_2") (pintype "passive"))
    )
    (net (code "45") (name "Net-(IC2-GPA4)") (class "Default")
      (node (ref "IC2") (pin "25") (pinfunction "GPA4_25") (pintype "bidirectional"))
      (node (ref "J7") (pin "3") (pinfunction "3_3") (pintype "passive"))
    )
    (net (code "46") (name "Net-(IC2-GPA5)") (class "Default")
      (node (ref "IC2") (pin "26") (pinfunction "GPA5_26") (pintype "bidirectional"))
      (node (ref "J7") (pin "4") (pinfunction "4_4") (pintype "passive"))
    )
    (net (code "47") (name "Net-(IC2-GPA6)") (class "Default")
      (node (ref "IC2") (pin "27") (pinfunction "GPA6_27") (pintype "bidirectional"))
      (node (ref "J7") (pin "5") (pinfunction "5_5") (pintype "passive"))
    )
    (net (code "48") (name "Net-(IC2-GPA7)") (class "Default")
      (node (ref "IC2") (pin "28") (pinfunction "GPA7_28") (pintype "bidirectional"))
      (node (ref "J7") (pin "6") (pinfunction "6_6") (pintype "passive"))
    )
    (net (code "49") (name "Net-(IC2-SCL)") (class "Default")
      (node (ref "IC2") (pin "12") (pinfunction "SCL_12") (pintype "input"))
      (node (ref "R2") (pin "2") (pinfunction "2_2") (pintype "passive"))
    )
    (net (code "50") (name "Net-(IC2-SDA)") (class "Default")
      (node (ref "IC2") (pin "13") (pinfunction "SDA_13") (pintype "bidirectional"))
      (node (ref "R3") (pin "2") (pinfunction "2_2") (pintype "passive"))
    )
    (net (code "51") (name "Net-(IC2-~{RESET})") (class "Default")
      (node (ref "IC2") (pin "18") (pinfunction "~{RESET}_18") (pintype "input"))
      (node (ref "R20") (pin "1") (pinfunction "1_1") (pintype "passive"))
    )
    (net (code "52") (name "Net-(JP1-Pad1)") (class "Default")
      (node (ref "JP1") (pin "1") (pinfunction "1_1") (pintype "passive"))
      (node (ref "U$1") (pin "103") (pinfunction "C5_103") (pintype "bidirectional"))
      (node (ref "U$1") (pin "67") (pinfunction "C5_67") (pintype "bidirectional"))
      (node (ref "U$1") (pin "C5") (pinfunction "C5_C5") (pintype "bidirectional"))
    )
    (net (code "53") (name "Net-(JP2-Pad2)") (class "Default")
      (node (ref "JP2") (pin "2") (pinfunction "2_2") (pintype "passive"))
      (node (ref "U$1") (pin "12") (pinfunction "A0_12") (pintype "bidirectional"))
      (node (ref "U$1") (pin "48") (pinfunction "A0_48") (pintype "bidirectional"))
      (node (ref "U$1") (pin "A0") (pinfunction "A0_A0") (pintype "bidirectional"))
    )
    (net (code "54") (name "Net-(JP4-Pad2)") (class "Default")
      (node (ref "JP4") (pin "2") (pinfunction "2_2") (pintype "passive"))
      (node (ref "U$1") (pin "11") (pinfunction "A1_11") (pintype "bidirectional"))
      (node (ref "U$1") (pin "47") (pinfunction "A1_47") (pintype "bidirectional"))
      (node (ref "U$1") (pin "A1") (pinfunction "A1_A1") (pintype "bidirectional"))
    )
    (net (code "55") (name "Net-(JP5-Pad1)") (class "Default")
      (node (ref "JP5") (pin "1") (pinfunction "1_1") (pintype "passive"))
      (node (ref "U$1") (pin "104") (pinfunction "C4_104") (pintype "bidirectional"))
      (node (ref "U$1") (pin "68") (pinfunction "C4_68") (pintype "bidirectional"))
      (node (ref "U$1") (pin "C4") (pinfunction "C4_C4") (pintype "bidirectional"))
    )
    (net (code "56") (name "Net-(JP13-Pad2)") (class "Default")
      (node (ref "JP13") (pin "2") (pinfunction "2_2") (pintype "passive"))
      (node (ref "U$1") (pin "10") (pinfunction "A2_10") (pintype "bidirectional"))
      (node (ref "U$1") (pin "46") (pinfunction "A2_46") (pintype "bidirectional"))
      (node (ref "U$1") (pin "A2") (pinfunction "A2_A2") (pintype "bidirectional"))
    )
    (net (code "57") (name "Net-(JP14-Pad2)") (class "Default")
      (node (ref "JP14") (pin "2") (pinfunction "2_2") (pintype "passive"))
      (node (ref "U$1") (pin "45") (pinfunction "A3_45") (pintype "bidirectional"))
      (node (ref "U$1") (pin "9") (pinfunction "A3_9") (pintype "bidirectional"))
      (node (ref "U$1") (pin "A3") (pinfunction "A3_A3") (pintype "bidirectional"))
    )
    (net (code "58") (name "Net-(JP17-Pad2)") (class "Default")
      (node (ref "JP17") (pin "2") (pinfunction "2_2") (pintype "passive"))
      (node (ref "U$1") (pin "44") (pinfunction "A4_44") (pintype "bidirectional"))
      (node (ref "U$1") (pin "8") (pinfunction "A4_8") (pintype "bidirectional"))
      (node (ref "U$1") (pin "A4") (pinfunction "A4_A4") (pintype "bidirectional"))
    )
    (net (code "59") (name "Net-(JP18-Pad2)") (class "Default")
      (node (ref "JP18") (pin "2") (pinfunction "2_2") (pintype "passive"))
      (node (ref "U$1") (pin "43") (pinfunction "A5_43") (pintype "bidirectional"))
      (node (ref "U$1") (pin "7") (pinfunction "A5_7") (pintype "bidirectional"))
      (node (ref "U$1") (pin "A5") (pinfunction "A5_A5") (pintype "bidirectional"))
    )
    (net (code "60") (name "Net-(JP19-Pad1)") (class "Default")
      (node (ref "JP19") (pin "1") (pinfunction "1_1") (pintype "passive"))
      (node (ref "U$1") (pin "63") (pinfunction "D3_63") (pintype "bidirectional"))
      (node (ref "U$1") (pin "99") (pinfunction "D3_99") (pintype "bidirectional"))
      (node (ref "U$1") (pin "D3") (pinfunction "D3_D3") (pintype "bidirectional"))
    )
    (net (code "61") (name "Net-(JP20-Pad1)") (class "Default")
      (node (ref "JP20") (pin "1") (pinfunction "1_1") (pintype "passive"))
      (node (ref "U$1") (pin "100") (pinfunction "D2_100") (pintype "bidirectional"))
      (node (ref "U$1") (pin "64") (pinfunction "D2_64") (pintype "bidirectional"))
      (node (ref "U$1") (pin "D2") (pinfunction "D2_D2") (pintype "bidirectional"))
    )
    (net (code "62") (name "Net-(JP21-Pad1)") (class "Default")
      (node (ref "JP21") (pin "1") (pinfunction "1_1") (pintype "passive"))
      (node (ref "U$1") (pin "101") (pinfunction "D1_101") (pintype "bidirectional"))
      (node (ref "U$1") (pin "65") (pinfunction "D1_65") (pintype "bidirectional"))
      (node (ref "U$1") (pin "D1") (pinfunction "D1_D1") (pintype "bidirectional"))
    )
    (net (code "63") (name "Net-(JP22-Pad1)") (class "Default")
      (node (ref "JP22") (pin "1") (pinfunction "1_1") (pintype "passive"))
      (node (ref "U$1") (pin "102") (pinfunction "D0_102") (pintype "bidirectional"))
      (node (ref "U$1") (pin "66") (pinfunction "D0_66") (pintype "bidirectional"))
      (node (ref "U$1") (pin "D0") (pinfunction "D0_D0") (pintype "bidirectional"))
    )
    (net (code "64") (name "Net-(JP25-Pad1)") (class "Default")
      (node (ref "JP25") (pin "1") (pinfunction "1_1") (pintype "passive"))
      (node (ref "U$1") (pin "61") (pinfunction "D5_61") (pintype "bidirectional"))
      (node (ref "U$1") (pin "97") (pinfunction "D5_97") (pintype "bidirectional"))
      (node (ref "U$1") (pin "D5") (pinfunction "D5_D5") (pintype "bidirectional"))
    )
    (net (code "65") (name "Net-(JP26-Pad1)") (class "Default")
      (node (ref "JP26") (pin "1") (pinfunction "1_1") (pintype "passive"))
      (node (ref "U$1") (pin "62") (pinfunction "D4_62") (pintype "bidirectional"))
      (node (ref "U$1") (pin "98") (pinfunction "D4_98") (pintype "bidirectional"))
      (node (ref "U$1") (pin "D4") (pinfunction "D4_D4") (pintype "bidirectional"))
    )
    (net (code "66") (name "Net-(Q3-G)") (class "Default")
      (node (ref "Q3") (pin "1") (pinfunction "G_1") (pintype "passive"))
      (node (ref "R23") (pin "2") (pinfunction "2_2") (pintype "passive"))
      (node (ref "R33") (pin "1") (pinfunction "1_1") (pintype "passive"))
    )
    (net (code "67") (name "Net-(Q4-G)") (class "Default")
      (node (ref "Q4") (pin "1") (pinfunction "G_1") (pintype "passive"))
      (node (ref "R27") (pin "2") (pinfunction "2_2") (pintype "passive"))
      (node (ref "R32") (pin "1") (pinfunction "1_1") (pintype "passive"))
    )
    (net (code "68") (name "Net-(Q5-G)") (class "Default")
      (node (ref "Q5") (pin "1") (pinfunction "G_1") (pintype "passive"))
      (node (ref "R24") (pin "2") (pinfunction "2_2") (pintype "passive"))
      (node (ref "R30") (pin "1") (pinfunction "1_1") (pintype "passive"))
    )
    (net (code "69") (name "Net-(Q6-G)") (class "Default")
      (node (ref "Q6") (pin "1") (pinfunction "G_1") (pintype "passive"))
      (node (ref "R25") (pin "2") (pinfunction "2_2") (pintype "passive"))
      (node (ref "R31") (pin "1") (pinfunction "1_1") (pintype "passive"))
    )
    (net (code "70") (name "Net-(U$1-B0-Pad18)") (class "Default")
      (node (ref "U$1") (pin "18") (pinfunction "B0_18") (pintype "bidirectional"))
      (node (ref "U$1") (pin "54") (pinfunction "B0_54") (pintype "bidirectional"))
      (node (ref "U$1") (pin "B0") (pinfunction "B0_B0") (pintype "bidirectional"))
    )
    (net (code "71") (name "Net-(U$1-B1-Pad17)") (class "Default")
      (node (ref "U$1") (pin "17") (pinfunction "B1_17") (pintype "bidirectional"))
      (node (ref "U$1") (pin "53") (pinfunction "B1_53") (pintype "bidirectional"))
      (node (ref "U$1") (pin "B1") (pinfunction "B1_B1") (pintype "bidirectional"))
    )
    (net (code "72") (name "Net-(U$1-B2-Pad16)") (class "Default")
      (node (ref "U$1") (pin "16") (pinfunction "B2_16") (pintype "bidirectional"))
      (node (ref "U$1") (pin "52") (pinfunction "B2_52") (pintype "bidirectional"))
      (node (ref "U$1") (pin "B2") (pinfunction "B2_B2") (pintype "bidirectional"))
    )
    (net (code "73") (name "Net-(U$1-B3-Pad15)") (class "Default")
      (node (ref "U$1") (pin "15") (pinfunction "B3_15") (pintype "bidirectional"))
      (node (ref "U$1") (pin "51") (pinfunction "B3_51") (pintype "bidirectional"))
      (node (ref "U$1") (pin "B3") (pinfunction "B3_B3") (pintype "bidirectional"))
    )
    (net (code "74") (name "Net-(U$1-B4-Pad14)") (class "Default")
      (node (ref "U$1") (pin "14") (pinfunction "B4_14") (pintype "bidirectional"))
      (node (ref "U$1") (pin "50") (pinfunction "B4_50") (pintype "bidirectional"))
      (node (ref "U$1") (pin "B4") (pinfunction "B4_B4") (pintype "bidirectional"))
    )
    (net (code "75") (name "Net-(U$1-B5-Pad13)") (class "Default")
      (node (ref "U$1") (pin "13") (pinfunction "B5_13") (pintype "bidirectional"))
      (node (ref "U$1") (pin "49") (pinfunction "B5_49") (pintype "bidirectional"))
      (node (ref "U$1") (pin "B5") (pinfunction "B5_B5") (pintype "bidirectional"))
    )
    (net (code "76") (name "Net-(U$1-C0-Pad108)") (class "Default")
      (node (ref "U$1") (pin "108") (pinfunction "C0_108") (pintype "bidirectional"))
      (node (ref "U$1") (pin "72") (pinfunction "C0_72") (pintype "bidirectional"))
      (node (ref "U$1") (pin "C0") (pinfunction "C0_C0") (pintype "bidirectional"))
    )
    (net (code "77") (name "Net-(U$1-C1-Pad107)") (class "Default")
      (node (ref "U$1") (pin "107") (pinfunction "C1_107") (pintype "bidirectional"))
      (node (ref "U$1") (pin "71") (pinfunction "C1_71") (pintype "bidirectional"))
      (node (ref "U$1") (pin "C1") (pinfunction "C1_C1") (pintype "bidirectional"))
    )
    (net (code "78") (name "Net-(U$1-C2-Pad106)") (class "Default")
      (node (ref "U$1") (pin "106") (pinfunction "C2_106") (pintype "bidirectional"))
      (node (ref "U$1") (pin "70") (pinfunction "C2_70") (pintype "bidirectional"))
      (node (ref "U$1") (pin "C2") (pinfunction "C2_C2") (pintype "bidirectional"))
    )
    (net (code "79") (name "Net-(U$1-C3-Pad105)") (class "Default")
      (node (ref "U$1") (pin "105") (pinfunction "C3_105") (pintype "bidirectional"))
      (node (ref "U$1") (pin "69") (pinfunction "C3_69") (pintype "bidirectional"))
      (node (ref "U$1") (pin "C3") (pinfunction "C3_C3") (pintype "bidirectional"))
    )
    (net (code "80") (name "Net-(U$1-D6-Pad60)") (class "Default")
      (node (ref "U$1") (pin "60") (pinfunction "D6_60") (pintype "bidirectional"))
      (node (ref "U$1") (pin "96") (pinfunction "D6_96") (pintype "bidirectional"))
      (node (ref "U$1") (pin "D6") (pinfunction "D6_D6") (pintype "bidirectional"))
    )
    (net (code "81") (name "Net-(U$1-D7-Pad59)") (class "Default")
      (node (ref "U$1") (pin "59") (pinfunction "D7_59") (pintype "bidirectional"))
      (node (ref "U$1") (pin "95") (pinfunction "D7_95") (pintype "bidirectional"))
      (node (ref "U$1") (pin "D7") (pinfunction "D7_D7") (pintype "bidirectional"))
    )
    (net (code "82") (name "Net-(U$1-DAC-Pad42)") (class "Default")
      (node (ref "U$1") (pin "42") (pinfunction "DAC_42") (pintype "bidirectional"))
      (node (ref "U$1") (pin "6") (pinfunction "DAC_6") (pintype "bidirectional"))
      (node (ref "U$1") (pin "DAC") (pinfunction "DAC_DAC") (pintype "bidirectional"))
    )
    (net (code "83") (name "Net-(U$1-PadRST)") (class "Default")
      (node (ref "U$1") (pin "56") (pinfunction "RST_56") (pintype "bidirectional"))
      (node (ref "U$1") (pin "92") (pinfunction "RST_92") (pintype "bidirectional"))
      (node (ref "U$1") (pin "RST") (pinfunction "RST_RST") (pintype "bidirectional"))
    )
    (net (code "84") (name "Net-(U$1-PadRX)") (class "Default")
      (node (ref "U$1") (pin "4") (pinfunction "RX_4") (pintype "bidirectional"))
      (node (ref "U$1") (pin "40") (pinfunction "RX_40") (pintype "bidirectional"))
      (node (ref "U$1") (pin "RX") (pinfunction "RX_RX") (pintype "bidirectional"))
    )
    (net (code "85") (name "Net-(U$1-PadTX)") (class "Default")
      (node (ref "U$1") (pin "3") (pinfunction "TX_3") (pintype "bidirectional"))
      (node (ref "U$1") (pin "39") (pinfunction "TX_39") (pintype "bidirectional"))
      (node (ref "U$1") (pin "TX") (pinfunction "TX_TX") (pintype "bidirectional"))
    )
    (net (code "86") (name "Net-(U$1-PadVBAT)") (class "Default")
      (node (ref "U$1") (pin "57") (pinfunction "VBAT_57") (pintype "passive"))
      (node (ref "U$1") (pin "93") (pinfunction "VBAT_93") (pintype "passive"))
      (node (ref "U$1") (pin "VBAT") (pinfunction "VBAT_VBAT") (pintype "passive"))
    )
    (net (code "87") (name "Net-(U$1-PadWKP)") (class "Default")
      (node (ref "U$1") (pin "41") (pinfunction "WKP_41") (pintype "bidirectional"))
      (node (ref "U$1") (pin "5") (pinfunction "WKP_5") (pintype "bidirectional"))
      (node (ref "U$1") (pin "WKP") (pinfunction "WKP_WKP") (pintype "bidirectional"))
    )
    (net (code "88") (name "Net-(U2-BST)") (class "Default")
      (node (ref "C7") (pin "1") (pinfunction "1_1") (pintype "passive"))
      (node (ref "U2") (pin "1") (pinfunction "BST_1") (pintype "bidirectional"))
    )
    (net (code "89") (name "Net-(U2-PGOOD)") (class "Default")
      (node (ref "R34") (pin "1") (pinfunction "1_1") (pintype "passive"))
      (node (ref "U2") (pin "4") (pinfunction "PGOOD_4") (pintype "bidirectional"))
    )
    (net (code "90") (name "Net-(U2-SW)") (class "Default")
      (node (ref "C7") (pin "2") (pinfunction "2_2") (pintype "passive"))
      (node (ref "D9") (pin "CATHODE") (pinfunction "CATHODE_CATHODE") (pintype "passive"))
      (node (ref "L4") (pin "1") (pinfunction "1_1") (pintype "passive"))
      (node (ref "U2") (pin "8") (pinfunction "SW_8") (pintype "bidirectional"))
    )
    (net (code "91") (name "Net-(U?1-AOUT1)") (class "Default")
      (node (ref "J4") (pin "1") (pinfunction "1_1") (pintype "passive"))
      (node (ref "U?1") (pin "5") (pinfunction "AOUT1_5") (pintype "bidirectional"))
    )
    (net (code "92") (name "Net-(U?1-AOUT2)") (class "Default")
      (node (ref "J4") (pin "2") (pinfunction "2_2") (pintype "passive"))
      (node (ref "U?1") (pin "7") (pinfunction "AOUT2_7") (pintype "bidirectional"))
    )
    (net (code "93") (name "Net-(U?1-AVREF)") (class "Default")
      (node (ref "R15") (pin "3") (pinfunction "3_3") (pintype "bidirectional"))
      (node (ref "U?1") (pin "12") (pinfunction "AVREF_12") (pintype "bidirectional"))
      (node (ref "U?1") (pin "13") (pinfunction "BVREF_13") (pintype "bidirectional"))
    )
    (net (code "94") (name "Net-(U?1-BOUT1)") (class "Default")
      (node (ref "J4") (pin "4") (pinfunction "4_4") (pintype "passive"))
      (node (ref "U?1") (pin "10") (pinfunction "BOUT1_10") (pintype "bidirectional"))
    )
    (net (code "95") (name "Net-(U?1-BOUT2)") (class "Default")
      (node (ref "J4") (pin "3") (pinfunction "3_3") (pintype "passive"))
      (node (ref "U?1") (pin "8") (pinfunction "BOUT2_8") (pintype "bidirectional"))
    )
    (net (code "96") (name "Net-(U?1-ISENA)") (class "Default")
      (node (ref "R9") (pin "1") (pinfunction "1_1") (pintype "passive"))
      (node (ref "U?1") (pin "6") (pinfunction "ISENA_6") (pintype "bidirectional"))
    )
    (net (code "97") (name "Net-(U?1-ISENB)") (class "Default")
      (node (ref "R8") (pin "1") (pinfunction "1_1") (pintype "passive"))
      (node (ref "U?1") (pin "9") (pinfunction "ISENB_9") (pintype "bidirectional"))
    )
    (net (code "98") (name "Net-(U?1-NRESET)") (class "Default")
      (node (ref "R12") (pin "2") (pinfunction "2_2") (pintype "passive"))
      (node (ref "U?1") (pin "16") (pinfunction "NRESET_16") (pintype "bidirectional"))
      (node (ref "U?1") (pin "17") (pinfunction "NSLEEP_17") (pintype "bidirectional"))
    )
    (net (code "99") (name "Net-(U?2-OUTPUT1)") (class "Default")
      (node (ref "D4") (pin "A") (pinfunction "A_A") (pintype "passive"))
      (node (ref "D8") (pin "C") (pinfunction "C_C") (pintype "passive"))
      (node (ref "J5") (pin "1") (pinfunction "1_1") (pintype "passive"))
      (node (ref "U?2") (pin "2") (pinfunction "OUTPUT1_2") (pintype "bidirectional"))
    )
    (net (code "100") (name "Net-(U?2-OUTPUT2)") (class "Default")
      (node (ref "D3") (pin "A") (pinfunction "A_A") (pintype "passive"))
      (node (ref "D7") (pin "C") (pinfunction "C_C") (pintype "passive"))
      (node (ref "J5") (pin "2") (pinfunction "2_2") (pintype "passive"))
      (node (ref "U?2") (pin "3") (pinfunction "OUTPUT2_3") (pintype "bidirectional"))
    )
    (net (code "101") (name "Net-(U?2-OUTPUT3)") (class "Default")
      (node (ref "D2") (pin "A") (pinfunction "A_A") (pintype "passive"))
      (node (ref "D6") (pin "C") (pinfunction "C_C") (pintype "passive"))
      (node (ref "J6") (pin "1") (pinfunction "1_1") (pintype "passive"))
      (node (ref "U?2") (pin "13") (pinfunction "OUTPUT3_13") (pintype "bidirectional"))
    )
    (net (code "102") (name "Net-(U?2-OUTPUT4)") (class "Default")
      (node (ref "D1") (pin "A") (pinfunction "A_A") (pintype "passive"))
      (node (ref "D5") (pin "C") (pinfunction "C_C") (pintype "passive"))
      (node (ref "J6") (pin "2") (pinfunction "2_2") (pintype "passive"))
      (node (ref "U?2") (pin "14") (pinfunction "OUTPUT4_14") (pintype "bidirectional"))
    )
    (net (code "103") (name "Net-(U?3-AOUT1)") (class "Default")
      (node (ref "J2") (pin "1") (pinfunction "1_1") (pintype "passive"))
      (node (ref "U?3") (pin "5") (pinfunction "AOUT1_5") (pintype "bidirectional"))
    )
    (net (code "104") (name "Net-(U?3-AOUT2)") (class "Default")
      (node (ref "J2") (pin "2") (pinfunction "2_2") (pintype "passive"))
      (node (ref "U?3") (pin "7") (pinfunction "AOUT2_7") (pintype "bidirectional"))
    )
    (net (code "105") (name "Net-(U?3-AVREF)") (class "Default")
      (node (ref "R14") (pin "3") (pinfunction "3_3") (pintype "bidirectional"))
      (node (ref "U?3") (pin "12") (pinfunction "AVREF_12") (pintype "bidirectional"))
      (node (ref "U?3") (pin "13") (pinfunction "BVREF_13") (pintype "bidirectional"))
    )
    (net (code "106") (name "Net-(U?3-BOUT1)") (class "Default")
      (node (ref "J2") (pin "4") (pinfunction "4_4") (pintype "passive"))
      (node (ref "U?3") (pin "10") (pinfunction "BOUT1_10") (pintype "bidirectional"))
    )
    (net (code "107") (name "Net-(U?3-BOUT2)") (class "Default")
      (node (ref "J2") (pin "3") (pinfunction "3_3") (pintype "passive"))
      (node (ref "U?3") (pin "8") (pinfunction "BOUT2_8") (pintype "bidirectional"))
    )
    (net (code "108") (name "Net-(U?3-ISENA)") (class "Default")
      (node (ref "R7") (pin "1") (pinfunction "1_1") (pintype "passive"))
      (node (ref "U?3") (pin "6") (pinfunction "ISENA_6") (pintype "bidirectional"))
    )
    (net (code "109") (name "Net-(U?3-ISENB)") (class "Default")
      (node (ref "R6") (pin "1") (pinfunction "1_1") (pintype "passive"))
      (node (ref "U?3") (pin "9") (pinfunction "ISENB_9") (pintype "bidirectional"))
    )
    (net (code "110") (name "Net-(U?3-NRESET)") (class "Default")
      (node (ref "R10") (pin "2") (pinfunction "2_2") (pintype "passive"))
      (node (ref "U?3") (pin "16") (pinfunction "NRESET_16") (pintype "bidirectional"))
      (node (ref "U?3") (pin "17") (pinfunction "NSLEEP_17") (pintype "bidirectional"))
    )
    (net (code "111") (name "VIN") (class "Default")
      (node (ref "C10") (pin "1") (pinfunction "1_1") (pintype "passive"))
      (node (ref "C17") (pin "1") (pinfunction "ANODE_1") (pintype "passive"))
      (node (ref "C18") (pin "1") (pinfunction "ANODE_1") (pintype "passive"))
      (node (ref "C19") (pin "+") (pinfunction "+_+") (pintype "passive"))
      (node (ref "C20") (pin "+") (pinfunction "+_+") (pintype "passive"))
      (node (ref "C21") (pin "1") (pinfunction "ANODE_1") (pintype "passive"))
      (node (ref "C22") (pin "+") (pinfunction "+_+") (pintype "passive"))
      (node (ref "C23") (pin "+") (pinfunction "+_+") (pintype "passive"))
      (node (ref "C24") (pin "1") (pinfunction "ANODE_1") (pintype "passive"))
      (node (ref "C25") (pin "1") (pinfunction "ANODE_1") (pintype "passive"))
      (node (ref "C4") (pin "2") (pinfunction "CATHODE_2") (pintype "passive"))
      (node (ref "C5") (pin "2") (pinfunction "CATHODE_2") (pintype "passive"))
      (node (ref "D1") (pin "C") (pinfunction "C_C") (pintype "passive"))
      (node (ref "D10") (pin "CATHODE") (pinfunction "CATHODE_CATHODE") (pintype "bidirectional"))
      (node (ref "D2") (pin "C") (pinfunction "C_C") (pintype "passive"))
      (node (ref "D3") (pin "C") (pinfunction "C_C") (pintype "passive"))
      (node (ref "D4") (pin "C") (pinfunction "C_C") (pintype "passive"))
      (node (ref "J9") (pin "1") (pinfunction "1_1") (pintype "passive"))
      (node (ref "JP3") (pin "3") (pinfunction "3_3") (pintype "passive"))
      (node (ref "R11") (pin "1") (pinfunction "1_1") (pintype "passive"))
      (node (ref "R13") (pin "1") (pinfunction "1_1") (pintype "passive"))
      (node (ref "R34") (pin "2") (pinfunction "2_2") (pintype "passive"))
      (node (ref "U2") (pin "2") (pinfunction "VIN_2") (pintype "bidirectional"))
      (node (ref "U2") (pin "3") (pinfunction "EN_3") (pintype "bidirectional"))
      (node (ref "U?1") (pin "11") (pinfunction "VMB_11") (pintype "bidirectional"))
      (node (ref "U?1") (pin "4") (pinfunction "VMA_4") (pintype "bidirectional"))
      (node (ref "U?2") (pin "4") (pinfunction "VS_4") (pintype "bidirectional"))
      (node (ref "U?3") (pin "11") (pinfunction "VMB_11") (pintype "bidirectional"))
      (node (ref "U?3") (pin "4") (pinfunction "VMA_4") (pintype "bidirectional"))
    )
    (net (code "112") (name "unconnected-(IC2-GPB1-Pad2)") (class "Default")
      (node (ref "IC2") (pin "2") (pinfunction "GPB1_2") (pintype "bidirectional"))
    )
    (net (code "113") (name "unconnected-(IC2-INTA-Pad20)") (class "Default")
      (node (ref "IC2") (pin "20") (pinfunction "INTA_20") (pintype "output"))
    )
    (net (code "114") (name "unconnected-(IC2-INTB-Pad19)") (class "Default")
      (node (ref "IC2") (pin "19") (pinfunction "INTB_19") (pintype "output"))
    )
    (net (code "115") (name "unconnected-(U2-NC-Pad6)") (class "Default")
      (node (ref "U2") (pin "6") (pinfunction "NC_6") (pintype "bidirectional"))
    )
    (net (code "116") (name "unconnected-(U?1-DECAY-Pad19)") (class "Default")
      (node (ref "U?1") (pin "19") (pinfunction "DECAY_19") (pintype "bidirectional"))
    )
    (net (code "117") (name "unconnected-(U?1-NC-Pad23)") (class "Default")
      (node (ref "U?1") (pin "23") (pinfunction "NC_23") (pintype "bidirectional"))
    )
    (net (code "118") (name "unconnected-(U?1-NFAULT-Pad18)") (class "Default")
      (node (ref "U?1") (pin "18") (pinfunction "NFAULT_18") (pintype "bidirectional"))
    )
    (net (code "119") (name "unconnected-(U?1-NHOME-Pad27)") (class "Default")
      (node (ref "U?1") (pin "27") (pinfunction "NHOME_27") (pintype "bidirectional"))
    )
    (net (code "120") (name "unconnected-(U?3-DECAY-Pad19)") (class "Default")
      (node (ref "U?3") (pin "19") (pinfunction "DECAY_19") (pintype "bidirectional"))
    )
    (net (code "121") (name "unconnected-(U?3-NC-Pad23)") (class "Default")
      (node (ref "U?3") (pin "23") (pinfunction "NC_23") (pintype "bidirectional"))
    )
    (net (code "122") (name "unconnected-(U?3-NFAULT-Pad18)") (class "Default")
      (node (ref "U?3") (pin "18") (pinfunction "NFAULT_18") (pintype "bidirectional"))
    )
    (net (code "123") (name "unconnected-(U?3-NHOME-Pad27)") (class "Default")
      (node (ref "U?3") (pin "27") (pinfunction "NHOME_27") (pintype "bidirectional"))
    )
  )
)
